# eHorglass.net
KiCad netlist of a schematic drawn in Altium Designer
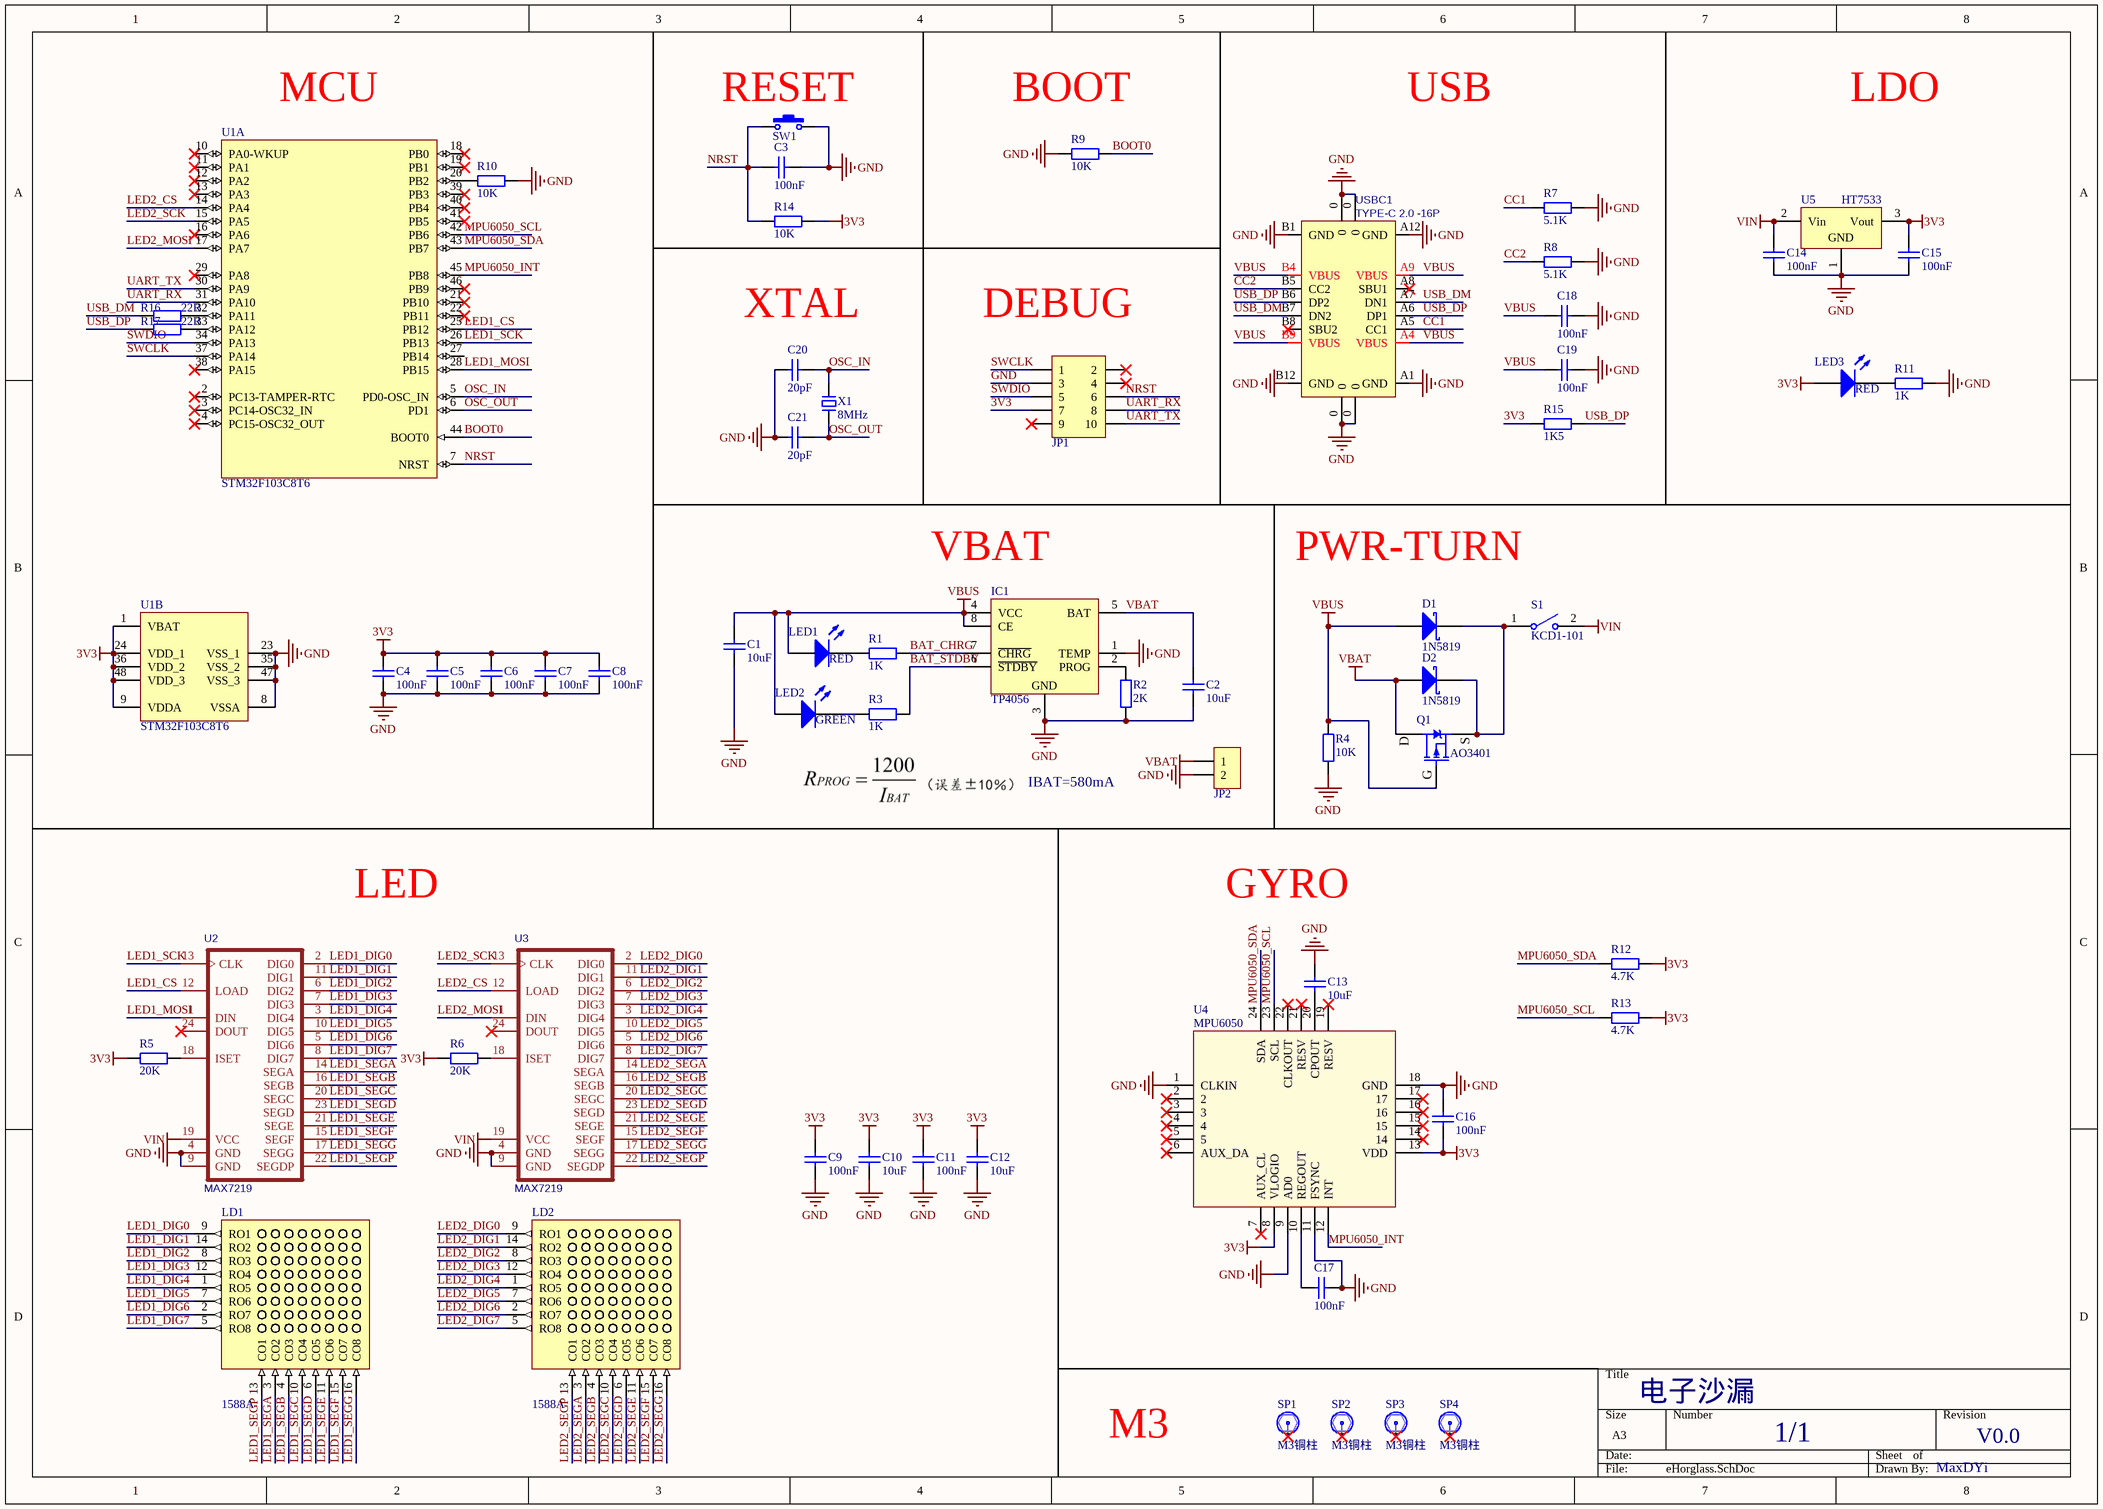
[diagram p0: eHorglass.SchDoc]

(export (version "E")
  (design (tool "Eeschema 10.0.6"))
  (components
    (comp (ref "C1")
      (value "10uF")
      (footprint "C0603_M")
      (description "贴片电容/MLCC电容")
      (libsource (lib "0.1 - 电阻-电容-电感-保险丝-晶振-晶体-磁珠-电位器-法拉电容-馈通电容") (part "C"))
    )
    (comp (ref "C2")
      (value "10uF")
      (footprint "C0603_M")
      (description "贴片电容/MLCC电容")
      (libsource (lib "0.1 - 电阻-电容-电感-保险丝-晶振-晶体-磁珠-电位器-法拉电容-馈通电容") (part "C"))
    )
    (comp (ref "C3")
      (value "100nF")
      (footprint "C0603_M")
      (description "贴片电容/MLCC电容")
      (libsource (lib "0.1 - 电阻-电容-电感-保险丝-晶振-晶体-磁珠-电位器-法拉电容-馈通电容") (part "C"))
    )
    (comp (ref "C4")
      (value "100nF")
      (footprint "C0603_M")
      (description "贴片电容/MLCC电容")
      (libsource (lib "0.1 - 电阻-电容-电感-保险丝-晶振-晶体-磁珠-电位器-法拉电容-馈通电容") (part "C"))
    )
    (comp (ref "C5")
      (value "100nF")
      (footprint "C0603_M")
      (description "贴片电容/MLCC电容")
      (libsource (lib "0.1 - 电阻-电容-电感-保险丝-晶振-晶体-磁珠-电位器-法拉电容-馈通电容") (part "C"))
    )
    (comp (ref "C6")
      (value "100nF")
      (footprint "C0603_M")
      (description "贴片电容/MLCC电容")
      (libsource (lib "0.1 - 电阻-电容-电感-保险丝-晶振-晶体-磁珠-电位器-法拉电容-馈通电容") (part "C"))
    )
    (comp (ref "C7")
      (value "100nF")
      (footprint "C0603_M")
      (description "贴片电容/MLCC电容")
      (libsource (lib "0.1 - 电阻-电容-电感-保险丝-晶振-晶体-磁珠-电位器-法拉电容-馈通电容") (part "C"))
    )
    (comp (ref "C8")
      (value "100nF")
      (footprint "C0603_M")
      (description "贴片电容/MLCC电容")
      (libsource (lib "0.1 - 电阻-电容-电感-保险丝-晶振-晶体-磁珠-电位器-法拉电容-馈通电容") (part "C"))
    )
    (comp (ref "C9")
      (value "100nF")
      (footprint "C0603_M")
      (description "贴片电容/MLCC电容")
      (libsource (lib "0.1 - 电阻-电容-电感-保险丝-晶振-晶体-磁珠-电位器-法拉电容-馈通电容") (part "C"))
    )
    (comp (ref "C10")
      (value "10uF")
      (footprint "C0603_M")
      (description "贴片电容/MLCC电容")
      (libsource (lib "0.1 - 电阻-电容-电感-保险丝-晶振-晶体-磁珠-电位器-法拉电容-馈通电容") (part "C"))
    )
    (comp (ref "C11")
      (value "100nF")
      (footprint "C0603_M")
      (description "贴片电容/MLCC电容")
      (libsource (lib "0.1 - 电阻-电容-电感-保险丝-晶振-晶体-磁珠-电位器-法拉电容-馈通电容") (part "C"))
    )
    (comp (ref "C12")
      (value "10uF")
      (footprint "C0603_M")
      (description "贴片电容/MLCC电容")
      (libsource (lib "0.1 - 电阻-电容-电感-保险丝-晶振-晶体-磁珠-电位器-法拉电容-馈通电容") (part "C"))
    )
    (comp (ref "C13")
      (value "10uF")
      (footprint "C0603_M")
      (description "贴片电容/MLCC电容")
      (libsource (lib "0.1 - 电阻-电容-电感-保险丝-晶振-晶体-磁珠-电位器-法拉电容-馈通电容") (part "C"))
    )
    (comp (ref "C14")
      (value "100nF")
      (footprint "C0603_M")
      (description "贴片电容/MLCC电容")
      (libsource (lib "0.1 - 电阻-电容-电感-保险丝-晶振-晶体-磁珠-电位器-法拉电容-馈通电容") (part "C"))
    )
    (comp (ref "C15")
      (value "100nF")
      (footprint "C0603_M")
      (description "贴片电容/MLCC电容")
      (libsource (lib "0.1 - 电阻-电容-电感-保险丝-晶振-晶体-磁珠-电位器-法拉电容-馈通电容") (part "C"))
    )
    (comp (ref "C16")
      (value "100nF")
      (footprint "C0603_M")
      (description "贴片电容/MLCC电容")
      (libsource (lib "0.1 - 电阻-电容-电感-保险丝-晶振-晶体-磁珠-电位器-法拉电容-馈通电容") (part "C"))
    )
    (comp (ref "C17")
      (value "100nF")
      (footprint "C0603_M")
      (description "贴片电容/MLCC电容")
      (libsource (lib "0.1 - 电阻-电容-电感-保险丝-晶振-晶体-磁珠-电位器-法拉电容-馈通电容") (part "C"))
    )
    (comp (ref "C18")
      (value "100nF")
      (footprint "C0603_M")
      (description "贴片电容/MLCC电容")
      (libsource (lib "0.1 - 电阻-电容-电感-保险丝-晶振-晶体-磁珠-电位器-法拉电容-馈通电容") (part "C"))
    )
    (comp (ref "C19")
      (value "100nF")
      (footprint "C0603_M")
      (description "贴片电容/MLCC电容")
      (libsource (lib "0.1 - 电阻-电容-电感-保险丝-晶振-晶体-磁珠-电位器-法拉电容-馈通电容") (part "C"))
    )
    (comp (ref "C20")
      (value "20pF")
      (footprint "C0603_M")
      (description "贴片电容/MLCC电容")
      (libsource (lib "0.1 - 电阻-电容-电感-保险丝-晶振-晶体-磁珠-电位器-法拉电容-馈通电容") (part "C"))
    )
    (comp (ref "C21")
      (value "20pF")
      (footprint "C0603_M")
      (description "贴片电容/MLCC电容")
      (libsource (lib "0.1 - 电阻-电容-电感-保险丝-晶振-晶体-磁珠-电位器-法拉电容-馈通电容") (part "C"))
    )
    (comp (ref "D1")
      (value "1N5819")
      (footprint "SOD-323")
      (description "肖特基二极管")
      (libsource (lib "0.2 - 二极管-TVS-ESD-整流桥-放电管") (part "1N5819"))
    )
    (comp (ref "D2")
      (value "1N5819")
      (footprint "SOD-323")
      (description "肖特基二极管")
      (libsource (lib "0.2 - 二极管-TVS-ESD-整流桥-放电管") (part "1N5819"))
    )
    (comp (ref "IC1")
      (value "TP4056")
      (footprint "SOIC-8_EP")
      (description "锂电池充电管理")
      (libsource (lib "0.7 - 电源类芯片") (part "TP4056"))
    )
    (comp (ref "JP1")
      (value "Header 5X2")
      (footprint "HDR2.54-LI-2x5P")
      (description "5*2P接插件")
      (libsource (lib "JD-Signal") (part "Header 5X2"))
    )
    (comp (ref "JP2")
      (value "HDR-1X2")
      (footprint "XH2.54-LI-2P")
      (description "2P接插件")
      (libsource (lib "5.5 - 2.54mm连接器(KF2EDGK_XH2.54_2.54排针排母)") (part "Header 2"))
    )
    (comp (ref "LD1")
      (value "1588A")
      (footprint "LED 8*8-32-FH")
      (description "共阴单色LED8*8点阵屏")
      (libsource (lib "1.3 - 数码管-TFT-OLED屏") (part "1588A"))
    )
    (comp (ref "LD2")
      (value "1588A")
      (footprint "LED 8*8-32-FH")
      (description "共阴单色LED8*8点阵屏")
      (libsource (lib "1.3 - 数码管-TFT-OLED屏") (part "1588A"))
    )
    (comp (ref "LED1")
      (value "RED")
      (footprint "LED0603_R")
      (description "贴片LED")
      (libsource (lib "0.3 - LED发光二极管-IR二极管_接收管-光耦") (part "LED"))
    )
    (comp (ref "LED2")
      (value "GREEN")
      (footprint "LED0603_G")
      (description "贴片LED")
      (libsource (lib "0.3 - LED发光二极管-IR二极管_接收管-光耦") (part "LED"))
    )
    (comp (ref "LED3")
      (value "RED")
      (footprint "LED0603_R")
      (description "贴片LED")
      (libsource (lib "0.3 - LED发光二极管-IR二极管_接收管-光耦") (part "LED"))
    )
    (comp (ref "Q1")
      (value "AO3401")
      (footprint "SOT23-3N")
      (description "P沟道 30V/4.2A")
      (libsource (lib "0.4 - 三极管-场效应管-可控硅") (part "AO3401"))
    )
    (comp (ref "R1")
      (value "1K")
      (footprint "R0603_M")
      (description "贴片电阻")
      (libsource (lib "0.1 - 电阻-电容-电感-保险丝-晶振-晶体-磁珠-电位器-法拉电容-馈通电容") (part "R"))
    )
    (comp (ref "R2")
      (value "2K")
      (footprint "R0603_M")
      (description "贴片电阻")
      (libsource (lib "0.1 - 电阻-电容-电感-保险丝-晶振-晶体-磁珠-电位器-法拉电容-馈通电容") (part "R"))
    )
    (comp (ref "R3")
      (value "1K")
      (footprint "R0603_M")
      (description "贴片电阻")
      (libsource (lib "0.1 - 电阻-电容-电感-保险丝-晶振-晶体-磁珠-电位器-法拉电容-馈通电容") (part "R"))
    )
    (comp (ref "R4")
      (value "10K")
      (footprint "R0603_M")
      (description "贴片电阻")
      (libsource (lib "0.1 - 电阻-电容-电感-保险丝-晶振-晶体-磁珠-电位器-法拉电容-馈通电容") (part "R"))
    )
    (comp (ref "R5")
      (value "20K")
      (footprint "R0603_M")
      (description "贴片电阻")
      (libsource (lib "0.1 - 电阻-电容-电感-保险丝-晶振-晶体-磁珠-电位器-法拉电容-馈通电容") (part "R"))
    )
    (comp (ref "R6")
      (value "20K")
      (footprint "R0603_M")
      (description "贴片电阻")
      (libsource (lib "0.1 - 电阻-电容-电感-保险丝-晶振-晶体-磁珠-电位器-法拉电容-馈通电容") (part "R"))
    )
    (comp (ref "R7")
      (value "5.1K")
      (footprint "R0603_M")
      (description "贴片电阻")
      (libsource (lib "0.1 - 电阻-电容-电感-保险丝-晶振-晶体-磁珠-电位器-法拉电容-馈通电容") (part "R"))
    )
    (comp (ref "R8")
      (value "5.1K")
      (footprint "R0603_M")
      (description "贴片电阻")
      (libsource (lib "0.1 - 电阻-电容-电感-保险丝-晶振-晶体-磁珠-电位器-法拉电容-馈通电容") (part "R"))
    )
    (comp (ref "R9")
      (value "10K")
      (footprint "R0603_M")
      (description "贴片电阻")
      (libsource (lib "0.1 - 电阻-电容-电感-保险丝-晶振-晶体-磁珠-电位器-法拉电容-馈通电容") (part "R"))
    )
    (comp (ref "R10")
      (value "10K")
      (footprint "R0603_M")
      (description "贴片电阻")
      (libsource (lib "0.1 - 电阻-电容-电感-保险丝-晶振-晶体-磁珠-电位器-法拉电容-馈通电容") (part "R"))
    )
    (comp (ref "R11")
      (value "1K")
      (footprint "R0603_M")
      (description "贴片电阻")
      (libsource (lib "0.1 - 电阻-电容-电感-保险丝-晶振-晶体-磁珠-电位器-法拉电容-馈通电容") (part "R"))
    )
    (comp (ref "R12")
      (value "4.7K")
      (footprint "R0603_M")
      (description "贴片电阻")
      (libsource (lib "0.1 - 电阻-电容-电感-保险丝-晶振-晶体-磁珠-电位器-法拉电容-馈通电容") (part "R"))
    )
    (comp (ref "R13")
      (value "4.7K")
      (footprint "R0603_M")
      (description "贴片电阻")
      (libsource (lib "0.1 - 电阻-电容-电感-保险丝-晶振-晶体-磁珠-电位器-法拉电容-馈通电容") (part "R"))
    )
    (comp (ref "R14")
      (value "10K")
      (footprint "R0603_M")
      (description "贴片电阻")
      (libsource (lib "0.1 - 电阻-电容-电感-保险丝-晶振-晶体-磁珠-电位器-法拉电容-馈通电容") (part "R"))
    )
    (comp (ref "R15")
      (value "1K5")
      (footprint "R0603_M")
      (description "贴片电阻")
      (libsource (lib "0.1 - 电阻-电容-电感-保险丝-晶振-晶体-磁珠-电位器-法拉电容-馈通电容") (part "R"))
    )
    (comp (ref "R16")
      (value "22R")
      (footprint "R0603_M")
      (description "贴片电阻")
      (libsource (lib "0.1 - 电阻-电容-电感-保险丝-晶振-晶体-磁珠-电位器-法拉电容-馈通电容") (part "R"))
    )
    (comp (ref "R17")
      (value "22R")
      (footprint "R0603_M")
      (description "贴片电阻")
      (libsource (lib "0.1 - 电阻-电容-电感-保险丝-晶振-晶体-磁珠-电位器-法拉电容-馈通电容") (part "R"))
    )
    (comp (ref "S1")
      (value "KCD1-101")
      (footprint "HDR2.54-LI-2P")
      (description "1路单刀船型开关")
      (libsource (lib "0.5 - 按键_开关_蜂鸣器_电池_测试点_Mark点_铜柱") (part "KCD1-101"))
    )
    (comp (ref "SP1")
      (value "M3铜柱")
      (footprint "M3x20+6_N")
      (description "铜柱")
      (libsource (lib "0.5 - 按键_开关_蜂鸣器_电池_测试点_Mark点_铜柱") (part "铜柱加头大焊盘"))
    )
    (comp (ref "SP2")
      (value "M3铜柱")
      (footprint "M3x20+6_N")
      (description "铜柱")
      (libsource (lib "0.5 - 按键_开关_蜂鸣器_电池_测试点_Mark点_铜柱") (part "铜柱加头大焊盘"))
    )
    (comp (ref "SP3")
      (value "M3铜柱")
      (footprint "M3x20+6_N")
      (description "铜柱")
      (libsource (lib "0.5 - 按键_开关_蜂鸣器_电池_测试点_Mark点_铜柱") (part "铜柱加头大焊盘"))
    )
    (comp (ref "SP4")
      (value "M3铜柱")
      (footprint "M3x20+6_N")
      (description "铜柱")
      (libsource (lib "0.5 - 按键_开关_蜂鸣器_电池_测试点_Mark点_铜柱") (part "铜柱加头大焊盘"))
    )
    (comp (ref "SW1")
      (value "3x6x5")
      (footprint "SW SMD-3*6*2.5")
      (description "3x6轻触开关")
      (libsource (lib "0.5 - 按键_开关_蜂鸣器_电池_测试点_Mark点_铜柱") (part "SW 3x6"))
    )
    (comp (ref "U1")
      (value "STM32F103C8T6")
      (footprint "LQFP48_N")
      (libsource (lib "2.4 - STM32 F1系列单片机") (part "STM32F103C8T6"))
    )
    (comp (ref "U2")
      (value "MAX7219")
      (footprint "SOIC-24W")
      (description "8位 LED驱动器")
      (libsource (lib "0.8 - 常见芯片") (part "MAX7219"))
    )
    (comp (ref "U3")
      (value "MAX7219")
      (footprint "SOIC-24W")
      (description "8位 LED驱动器")
      (libsource (lib "0.8 - 常见芯片") (part "MAX7219"))
    )
    (comp (ref "U4")
      (value "MPU6050")
      (footprint "QFN24-P50")
      (description "三轴加速度+三轴陀螺仪")
      (libsource (lib "0.9 - 传感器-存储器-模块") (part "MPU6050"))
    )
    (comp (ref "U5")
      (value "HT7533")
      (footprint "SOT89_N")
      (description "LDO线性稳压芯片")
      (libsource (lib "0.7 - 电源类芯片") (part "HT7533"))
    )
    (comp (ref "USBC1")
      (value "TYPE-C 2.0 -16P")
      (footprint "USB-C-SMD_16P")
      (description "USB2.0_Type-C_16Pin母座")
      (libsource (lib "0.6 - 电源_音频_USB Type-C_HDMI_XT60_5557_D-SUB_RJ45_SD-TF_SIM插座") (part "USB2.0_Type-C_16Pin"))
    )
    (comp (ref "X1")
      (value "8MHz")
      (footprint "OSC-5032-2P")
      (description "2脚无源晶振(谐振器）")
      (libsource (lib "0.1 - 电阻-电容-电感-保险丝-晶振-晶体-磁珠-电位器-法拉电容-馈通电容") (part "XTAL-2P"))
    )
  )
  (nets
    (net (code "1") (name "/BAT_CHRG") (class "Default")
      (node (ref "IC1") (pin "7") (pinfunction "~{CHRG}_7") (pintype "passive"))
      (node (ref "R1") (pin "1") (pinfunction "1_1") (pintype "passive"))
    )
    (net (code "2") (name "/BAT_STDBY") (class "Default")
      (node (ref "IC1") (pin "6") (pinfunction "~{STDBY}_6") (pintype "passive"))
      (node (ref "R3") (pin "1") (pinfunction "1_1") (pintype "passive"))
    )
    (net (code "3") (name "/BOOT0") (class "Default")
      (node (ref "R9") (pin "2") (pinfunction "2_2") (pintype "passive"))
      (node (ref "U1") (pin "44") (pinfunction "BOOT0_44") (pintype "input"))
    )
    (net (code "4") (name "/CC1") (class "Default")
      (node (ref "R7") (pin "2") (pinfunction "2_2") (pintype "passive"))
      (node (ref "USBC1") (pin "A5") (pinfunction "CC1_A5") (pintype "passive"))
    )
    (net (code "5") (name "/CC2") (class "Default")
      (node (ref "R8") (pin "2") (pinfunction "2_2") (pintype "passive"))
      (node (ref "USBC1") (pin "B5") (pinfunction "CC2_B5") (pintype "passive"))
    )
    (net (code "6") (name "/LED1_CS") (class "Default")
      (node (ref "U1") (pin "25") (pinfunction "PB12_25") (pintype "bidirectional"))
      (node (ref "U2") (pin "12") (pinfunction "LOAD_12") (pintype "passive"))
    )
    (net (code "7") (name "/LED1_DIG0") (class "Default")
      (node (ref "LD1") (pin "9") (pinfunction "RO1_9") (pintype "output"))
      (node (ref "U2") (pin "2") (pinfunction "DIG0_2") (pintype "passive"))
    )
    (net (code "8") (name "/LED1_DIG1") (class "Default")
      (node (ref "LD1") (pin "14") (pinfunction "RO2_14") (pintype "output"))
      (node (ref "U2") (pin "11") (pinfunction "DIG1_11") (pintype "passive"))
    )
    (net (code "9") (name "/LED1_DIG2") (class "Default")
      (node (ref "LD1") (pin "8") (pinfunction "RO3_8") (pintype "output"))
      (node (ref "U2") (pin "6") (pinfunction "DIG2_6") (pintype "passive"))
    )
    (net (code "10") (name "/LED1_DIG3") (class "Default")
      (node (ref "LD1") (pin "12") (pinfunction "RO4_12") (pintype "output"))
      (node (ref "U2") (pin "7") (pinfunction "DIG3_7") (pintype "passive"))
    )
    (net (code "11") (name "/LED1_DIG4") (class "Default")
      (node (ref "LD1") (pin "1") (pinfunction "RO5_1") (pintype "output"))
      (node (ref "U2") (pin "3") (pinfunction "DIG4_3") (pintype "passive"))
    )
    (net (code "12") (name "/LED1_DIG5") (class "Default")
      (node (ref "LD1") (pin "7") (pinfunction "RO6_7") (pintype "output"))
      (node (ref "U2") (pin "10") (pinfunction "DIG5_10") (pintype "passive"))
    )
    (net (code "13") (name "/LED1_DIG6") (class "Default")
      (node (ref "LD1") (pin "2") (pinfunction "RO7_2") (pintype "output"))
      (node (ref "U2") (pin "5") (pinfunction "DIG6_5") (pintype "passive"))
    )
    (net (code "14") (name "/LED1_DIG7") (class "Default")
      (node (ref "LD1") (pin "5") (pinfunction "RO8_5") (pintype "output"))
      (node (ref "U2") (pin "8") (pinfunction "DIG7_8") (pintype "passive"))
    )
    (net (code "15") (name "/LED1_MOSI") (class "Default")
      (node (ref "U1") (pin "28") (pinfunction "PB15_28") (pintype "bidirectional"))
      (node (ref "U2") (pin "1") (pinfunction "DIN_1") (pintype "passive"))
    )
    (net (code "16") (name "/LED1_SCK") (class "Default")
      (node (ref "U1") (pin "26") (pinfunction "PB13_26") (pintype "bidirectional"))
      (node (ref "U2") (pin "13") (pinfunction "CLK_13") (pintype "passive"))
    )
    (net (code "17") (name "/LED1_SEGA") (class "Default")
      (node (ref "LD1") (pin "3") (pinfunction "CO2_3") (pintype "input"))
      (node (ref "U2") (pin "14") (pinfunction "SEGA_14") (pintype "passive"))
    )
    (net (code "18") (name "/LED1_SEGB") (class "Default")
      (node (ref "LD1") (pin "4") (pinfunction "CO3_4") (pintype "input"))
      (node (ref "U2") (pin "16") (pinfunction "SEGB_16") (pintype "passive"))
    )
    (net (code "19") (name "/LED1_SEGC") (class "Default")
      (node (ref "LD1") (pin "10") (pinfunction "CO4_10") (pintype "input"))
      (node (ref "U2") (pin "20") (pinfunction "SEGC_20") (pintype "passive"))
    )
    (net (code "20") (name "/LED1_SEGD") (class "Default")
      (node (ref "LD1") (pin "6") (pinfunction "CO5_6") (pintype "input"))
      (node (ref "U2") (pin "23") (pinfunction "SEGD_23") (pintype "passive"))
    )
    (net (code "21") (name "/LED1_SEGE") (class "Default")
      (node (ref "LD1") (pin "11") (pinfunction "CO6_11") (pintype "input"))
      (node (ref "U2") (pin "21") (pinfunction "SEGE_21") (pintype "passive"))
    )
    (net (code "22") (name "/LED1_SEGF") (class "Default")
      (node (ref "LD1") (pin "15") (pinfunction "CO7_15") (pintype "input"))
      (node (ref "U2") (pin "15") (pinfunction "SEGF_15") (pintype "passive"))
    )
    (net (code "23") (name "/LED1_SEGG") (class "Default")
      (node (ref "LD1") (pin "16") (pinfunction "CO8_16") (pintype "input"))
      (node (ref "U2") (pin "17") (pinfunction "SEGG_17") (pintype "passive"))
    )
    (net (code "24") (name "/LED1_SEGP") (class "Default")
      (node (ref "LD1") (pin "13") (pinfunction "CO1_13") (pintype "input"))
      (node (ref "U2") (pin "22") (pinfunction "SEGDP_22") (pintype "passive"))
    )
    (net (code "25") (name "/LED2_CS") (class "Default")
      (node (ref "U1") (pin "14") (pinfunction "PA4_14") (pintype "bidirectional"))
      (node (ref "U3") (pin "12") (pinfunction "LOAD_12") (pintype "passive"))
    )
    (net (code "26") (name "/LED2_DIG0") (class "Default")
      (node (ref "LD2") (pin "9") (pinfunction "RO1_9") (pintype "output"))
      (node (ref "U3") (pin "2") (pinfunction "DIG0_2") (pintype "passive"))
    )
    (net (code "27") (name "/LED2_DIG1") (class "Default")
      (node (ref "LD2") (pin "14") (pinfunction "RO2_14") (pintype "output"))
      (node (ref "U3") (pin "11") (pinfunction "DIG1_11") (pintype "passive"))
    )
    (net (code "28") (name "/LED2_DIG2") (class "Default")
      (node (ref "LD2") (pin "8") (pinfunction "RO3_8") (pintype "output"))
      (node (ref "U3") (pin "6") (pinfunction "DIG2_6") (pintype "passive"))
    )
    (net (code "29") (name "/LED2_DIG3") (class "Default")
      (node (ref "LD2") (pin "12") (pinfunction "RO4_12") (pintype "output"))
      (node (ref "U3") (pin "7") (pinfunction "DIG3_7") (pintype "passive"))
    )
    (net (code "30") (name "/LED2_DIG4") (class "Default")
      (node (ref "LD2") (pin "1") (pinfunction "RO5_1") (pintype "output"))
      (node (ref "U3") (pin "3") (pinfunction "DIG4_3") (pintype "passive"))
    )
    (net (code "31") (name "/LED2_DIG5") (class "Default")
      (node (ref "LD2") (pin "7") (pinfunction "RO6_7") (pintype "output"))
      (node (ref "U3") (pin "10") (pinfunction "DIG5_10") (pintype "passive"))
    )
    (net (code "32") (name "/LED2_DIG6") (class "Default")
      (node (ref "LD2") (pin "2") (pinfunction "RO7_2") (pintype "output"))
      (node (ref "U3") (pin "5") (pinfunction "DIG6_5") (pintype "passive"))
    )
    (net (code "33") (name "/LED2_DIG7") (class "Default")
      (node (ref "LD2") (pin "5") (pinfunction "RO8_5") (pintype "output"))
      (node (ref "U3") (pin "8") (pinfunction "DIG7_8") (pintype "passive"))
    )
    (net (code "34") (name "/LED2_MOSI") (class "Default")
      (node (ref "U1") (pin "17") (pinfunction "PA7_17") (pintype "bidirectional"))
      (node (ref "U3") (pin "1") (pinfunction "DIN_1") (pintype "passive"))
    )
    (net (code "35") (name "/LED2_SCK") (class "Default")
      (node (ref "U1") (pin "15") (pinfunction "PA5_15") (pintype "bidirectional"))
      (node (ref "U3") (pin "13") (pinfunction "CLK_13") (pintype "passive"))
    )
    (net (code "36") (name "/LED2_SEGA") (class "Default")
      (node (ref "LD2") (pin "3") (pinfunction "CO2_3") (pintype "input"))
      (node (ref "U3") (pin "14") (pinfunction "SEGA_14") (pintype "passive"))
    )
    (net (code "37") (name "/LED2_SEGB") (class "Default")
      (node (ref "LD2") (pin "4") (pinfunction "CO3_4") (pintype "input"))
      (node (ref "U3") (pin "16") (pinfunction "SEGB_16") (pintype "passive"))
    )
    (net (code "38") (name "/LED2_SEGC") (class "Default")
      (node (ref "LD2") (pin "10") (pinfunction "CO4_10") (pintype "input"))
      (node (ref "U3") (pin "20") (pinfunction "SEGC_20") (pintype "passive"))
    )
    (net (code "39") (name "/LED2_SEGD") (class "Default")
      (node (ref "LD2") (pin "6") (pinfunction "CO5_6") (pintype "input"))
      (node (ref "U3") (pin "23") (pinfunction "SEGD_23") (pintype "passive"))
    )
    (net (code "40") (name "/LED2_SEGE") (class "Default")
      (node (ref "LD2") (pin "11") (pinfunction "CO6_11") (pintype "input"))
      (node (ref "U3") (pin "21") (pinfunction "SEGE_21") (pintype "passive"))
    )
    (net (code "41") (name "/LED2_SEGF") (class "Default")
      (node (ref "LD2") (pin "15") (pinfunction "CO7_15") (pintype "input"))
      (node (ref "U3") (pin "15") (pinfunction "SEGF_15") (pintype "passive"))
    )
    (net (code "42") (name "/LED2_SEGG") (class "Default")
      (node (ref "LD2") (pin "16") (pinfunction "CO8_16") (pintype "input"))
      (node (ref "U3") (pin "17") (pinfunction "SEGG_17") (pintype "passive"))
    )
    (net (code "43") (name "/LED2_SEGP") (class "Default")
      (node (ref "LD2") (pin "13") (pinfunction "CO1_13") (pintype "input"))
      (node (ref "U3") (pin "22") (pinfunction "SEGDP_22") (pintype "passive"))
    )
    (net (code "44") (name "/MPU6050_INT") (class "Default")
      (node (ref "U1") (pin "45") (pinfunction "PB8_45") (pintype "bidirectional"))
      (node (ref "U4") (pin "12") (pinfunction "INT_12") (pintype "passive"))
    )
    (net (code "45") (name "/MPU6050_SCL") (class "Default")
      (node (ref "R13") (pin "2") (pinfunction "2_2") (pintype "passive"))
      (node (ref "U1") (pin "42") (pinfunction "PB6_42") (pintype "bidirectional"))
      (node (ref "U4") (pin "23") (pinfunction "SCL_23") (pintype "passive"))
    )
    (net (code "46") (name "/MPU6050_SDA") (class "Default")
      (node (ref "R12") (pin "2") (pinfunction "2_2") (pintype "passive"))
      (node (ref "U1") (pin "43") (pinfunction "PB7_43") (pintype "bidirectional"))
      (node (ref "U4") (pin "24") (pinfunction "SDA_24") (pintype "passive"))
    )
    (net (code "47") (name "/NRST") (class "Default")
      (node (ref "C3") (pin "2") (pinfunction "2_2") (pintype "passive"))
      (node (ref "JP1") (pin "6") (pinfunction "6_6") (pintype "passive"))
      (node (ref "R14") (pin "1") (pinfunction "1_1") (pintype "passive"))
      (node (ref "SW1") (pin "1") (pinfunction "1_1") (pintype "passive"))
      (node (ref "U1") (pin "7") (pinfunction "NRST_7") (pintype "bidirectional"))
    )
    (net (code "48") (name "/OSC_IN") (class "Default")
      (node (ref "C20") (pin "2") (pinfunction "2_2") (pintype "passive"))
      (node (ref "U1") (pin "5") (pinfunction "PD0-OSC_IN_5") (pintype "bidirectional"))
      (node (ref "X1") (pin "2") (pinfunction "2_2") (pintype "passive"))
    )
    (net (code "49") (name "/OSC_OUT") (class "Default")
      (node (ref "C21") (pin "1") (pinfunction "1_1") (pintype "passive"))
      (node (ref "U1") (pin "6") (pinfunction "PD1_6") (pintype "bidirectional"))
      (node (ref "X1") (pin "1") (pinfunction "1_1") (pintype "passive"))
    )
    (net (code "50") (name "/SWCLK") (class "Default")
      (node (ref "JP1") (pin "1") (pinfunction "1_1") (pintype "passive"))
      (node (ref "U1") (pin "37") (pinfunction "PA14_37") (pintype "bidirectional"))
    )
    (net (code "51") (name "/SWDIO") (class "Default")
      (node (ref "JP1") (pin "5") (pinfunction "5_5") (pintype "passive"))
      (node (ref "U1") (pin "34") (pinfunction "PA13_34") (pintype "bidirectional"))
    )
    (net (code "52") (name "/UART_RX") (class "Default")
      (node (ref "JP1") (pin "8") (pinfunction "8_8") (pintype "passive"))
      (node (ref "U1") (pin "31") (pinfunction "PA10_31") (pintype "bidirectional"))
    )
    (net (code "53") (name "/UART_TX") (class "Default")
      (node (ref "JP1") (pin "10") (pinfunction "10_10") (pintype "passive"))
      (node (ref "U1") (pin "30") (pinfunction "PA9_30") (pintype "bidirectional"))
    )
    (net (code "54") (name "/USB_DM") (class "Default")
      (node (ref "R16") (pin "1") (pinfunction "1_1") (pintype "passive"))
      (node (ref "USBC1") (pin "A7") (pinfunction "DN1_A7") (pintype "passive"))
      (node (ref "USBC1") (pin "B7") (pinfunction "DN2_B7") (pintype "passive"))
    )
    (net (code "55") (name "/USB_DP") (class "Default")
      (node (ref "R15") (pin "2") (pinfunction "2_2") (pintype "passive"))
      (node (ref "R17") (pin "1") (pinfunction "1_1") (pintype "passive"))
      (node (ref "USBC1") (pin "A6") (pinfunction "DP1_A6") (pintype "passive"))
      (node (ref "USBC1") (pin "B6") (pinfunction "DP2_B6") (pintype "passive"))
    )
    (net (code "56") (name "3V3") (class "Default")
      (node (ref "C10") (pin "2") (pinfunction "2_2") (pintype "passive"))
      (node (ref "C11") (pin "2") (pinfunction "2_2") (pintype "passive"))
      (node (ref "C12") (pin "2") (pinfunction "2_2") (pintype "passive"))
      (node (ref "C15") (pin "2") (pinfunction "2_2") (pintype "passive"))
      (node (ref "C16") (pin "2") (pinfunction "2_2") (pintype "passive"))
      (node (ref "C4") (pin "2") (pinfunction "2_2") (pintype "passive"))
      (node (ref "C5") (pin "2") (pinfunction "2_2") (pintype "passive"))
      (node (ref "C6") (pin "2") (pinfunction "2_2") (pintype "passive"))
      (node (ref "C7") (pin "2") (pinfunction "2_2") (pintype "passive"))
      (node (ref "C8") (pin "2") (pinfunction "2_2") (pintype "passive"))
      (node (ref "C9") (pin "2") (pinfunction "2_2") (pintype "passive"))
      (node (ref "JP1") (pin "7") (pinfunction "7_7") (pintype "passive"))
      (node (ref "LED3") (pin "1") (pinfunction "A_1") (pintype "passive"))
      (node (ref "R12") (pin "1") (pinfunction "1_1") (pintype "passive"))
      (node (ref "R13") (pin "1") (pinfunction "1_1") (pintype "passive"))
      (node (ref "R14") (pin "2") (pinfunction "2_2") (pintype "passive"))
      (node (ref "R15") (pin "1") (pinfunction "1_1") (pintype "passive"))
      (node (ref "R5") (pin "2") (pinfunction "2_2") (pintype "passive"))
      (node (ref "R6") (pin "2") (pinfunction "2_2") (pintype "passive"))
      (node (ref "U1") (pin "1") (pinfunction "VBAT_1") (pintype "power_in"))
      (node (ref "U1") (pin "24") (pinfunction "VDD_1_24") (pintype "power_in"))
      (node (ref "U1") (pin "36") (pinfunction "VDD_2_36") (pintype "power_in"))
      (node (ref "U1") (pin "48") (pinfunction "VDD_3_48") (pintype "power_in"))
      (node (ref "U1") (pin "9") (pinfunction "VDDA_9") (pintype "power_in"))
      (node (ref "U4") (pin "13") (pinfunction "VDD_13") (pintype "passive"))
      (node (ref "U4") (pin "8") (pinfunction "VLOGIO_8") (pintype "passive"))
      (node (ref "U5") (pin "3") (pinfunction "Vout_3") (pintype "passive"))
    )
    (net (code "57") (name "GND") (class "Default")
      (node (ref "C1") (pin "1") (pinfunction "1_1") (pintype "passive"))
      (node (ref "C10") (pin "1") (pinfunction "1_1") (pintype "passive"))
      (node (ref "C11") (pin "1") (pinfunction "1_1") (pintype "passive"))
      (node (ref "C12") (pin "1") (pinfunction "1_1") (pintype "passive"))
      (node (ref "C13") (pin "1") (pinfunction "1_1") (pintype "passive"))
      (node (ref "C14") (pin "1") (pinfunction "1_1") (pintype "passive"))
      (node (ref "C15") (pin "1") (pinfunction "1_1") (pintype "passive"))
      (node (ref "C16") (pin "1") (pinfunction "1_1") (pintype "passive"))
      (node (ref "C17") (pin "1") (pinfunction "1_1") (pintype "passive"))
      (node (ref "C18") (pin "2") (pinfunction "2_2") (pintype "passive"))
      (node (ref "C19") (pin "2") (pinfunction "2_2") (pintype "passive"))
      (node (ref "C2") (pin "1") (pinfunction "1_1") (pintype "passive"))
      (node (ref "C20") (pin "1") (pinfunction "1_1") (pintype "passive"))
      (node (ref "C21") (pin "2") (pinfunction "2_2") (pintype "passive"))
      (node (ref "C3") (pin "1") (pinfunction "1_1") (pintype "passive"))
      (node (ref "C4") (pin "1") (pinfunction "1_1") (pintype "passive"))
      (node (ref "C5") (pin "1") (pinfunction "1_1") (pintype "passive"))
      (node (ref "C6") (pin "1") (pinfunction "1_1") (pintype "passive"))
      (node (ref "C7") (pin "1") (pinfunction "1_1") (pintype "passive"))
      (node (ref "C8") (pin "1") (pinfunction "1_1") (pintype "passive"))
      (node (ref "C9") (pin "1") (pinfunction "1_1") (pintype "passive"))
      (node (ref "IC1") (pin "1") (pinfunction "TEMP_1") (pintype "passive"))
      (node (ref "IC1") (pin "3") (pinfunction "GND_3") (pintype "passive"))
      (node (ref "JP1") (pin "3") (pinfunction "3_3") (pintype "passive"))
      (node (ref "JP2") (pin "2") (pinfunction "2_2") (pintype "passive"))
      (node (ref "R10") (pin "1") (pinfunction "1_1") (pintype "passive"))
      (node (ref "R11") (pin "1") (pinfunction "1_1") (pintype "passive"))
      (node (ref "R2") (pin "1") (pinfunction "1_1") (pintype "passive"))
      (node (ref "R4") (pin "1") (pinfunction "1_1") (pintype "passive"))
      (node (ref "R7") (pin "1") (pinfunction "1_1") (pintype "passive"))
      (node (ref "R8") (pin "1") (pinfunction "1_1") (pintype "passive"))
      (node (ref "R9") (pin "1") (pinfunction "1_1") (pintype "passive"))
      (node (ref "SW1") (pin "2") (pinfunction "2_2") (pintype "passive"))
      (node (ref "U1") (pin "23") (pinfunction "VSS_1_23") (pintype "power_in"))
      (node (ref "U1") (pin "35") (pinfunction "VSS_2_35") (pintype "power_in"))
      (node (ref "U1") (pin "47") (pinfunction "VSS_3_47") (pintype "power_in"))
      (node (ref "U1") (pin "8") (pinfunction "VSSA_8") (pintype "power_in"))
      (node (ref "U2") (pin "4") (pinfunction "GND_4") (pintype "passive"))
      (node (ref "U2") (pin "9") (pinfunction "GND_9") (pintype "passive"))
      (node (ref "U3") (pin "4") (pinfunction "GND_4") (pintype "passive"))
      (node (ref "U3") (pin "9") (pinfunction "GND_9") (pintype "passive"))
      (node (ref "U4") (pin "1") (pinfunction "CLKIN_1") (pintype "passive"))
      (node (ref "U4") (pin "11") (pinfunction "FSYNC_11") (pintype "passive"))
      (node (ref "U4") (pin "18") (pinfunction "GND_18") (pintype "passive"))
      (node (ref "U4") (pin "9") (pinfunction "AD0_9") (pintype "passive"))
      (node (ref "U5") (pin "1") (pinfunction "GND_1") (pintype "passive"))
      (node (ref "USBC1") (pin "0") (pinfunction "0_0") (pintype "passive"))
      (node (ref "USBC1") (pin "A1") (pinfunction "GND_A1") (pintype "passive"))
      (node (ref "USBC1") (pin "A12") (pinfunction "GND_A12") (pintype "passive"))
      (node (ref "USBC1") (pin "B1") (pinfunction "GND_B1") (pintype "passive"))
      (node (ref "USBC1") (pin "B12") (pinfunction "GND_B12") (pintype "passive"))
    )
    (net (code "58") (name "Net-(D1-K)") (class "Default")
      (node (ref "D1") (pin "2") (pinfunction "K_2") (pintype "passive"))
      (node (ref "D2") (pin "2") (pinfunction "K_2") (pintype "passive"))
      (node (ref "Q1") (pin "2") (pinfunction "S_2") (pintype "passive"))
      (node (ref "S1") (pin "1") (pinfunction "1_1") (pintype "passive"))
    )
    (net (code "59") (name "Net-(IC1-PROG)") (class "Default")
      (node (ref "IC1") (pin "2") (pinfunction "PROG_2") (pintype "passive"))
      (node (ref "R2") (pin "2") (pinfunction "2_2") (pintype "passive"))
    )
    (net (code "60") (name "Net-(LED1-K)") (class "Default")
      (node (ref "LED1") (pin "2") (pinfunction "K_2") (pintype "passive"))
      (node (ref "R1") (pin "2") (pinfunction "2_2") (pintype "passive"))
    )
    (net (code "61") (name "Net-(LED2-K)") (class "Default")
      (node (ref "LED2") (pin "2") (pinfunction "K_2") (pintype "passive"))
      (node (ref "R3") (pin "2") (pinfunction "2_2") (pintype "passive"))
    )
    (net (code "62") (name "Net-(LED3-K)") (class "Default")
      (node (ref "LED3") (pin "2") (pinfunction "K_2") (pintype "passive"))
      (node (ref "R11") (pin "2") (pinfunction "2_2") (pintype "passive"))
    )
    (net (code "63") (name "Net-(U1A-PA11)") (class "Default")
      (node (ref "R16") (pin "2") (pinfunction "2_2") (pintype "passive"))
      (node (ref "U1") (pin "32") (pinfunction "PA11_32") (pintype "bidirectional"))
    )
    (net (code "64") (name "Net-(U1A-PA12)") (class "Default")
      (node (ref "R17") (pin "2") (pinfunction "2_2") (pintype "passive"))
      (node (ref "U1") (pin "33") (pinfunction "PA12_33") (pintype "bidirectional"))
    )
    (net (code "65") (name "Net-(U1A-PB2)") (class "Default")
      (node (ref "R10") (pin "2") (pinfunction "2_2") (pintype "passive"))
      (node (ref "U1") (pin "20") (pinfunction "PB2_20") (pintype "bidirectional"))
    )
    (net (code "66") (name "Net-(U2-ISET)") (class "Default")
      (node (ref "R5") (pin "1") (pinfunction "1_1") (pintype "passive"))
      (node (ref "U2") (pin "18") (pinfunction "ISET_18") (pintype "passive"))
    )
    (net (code "67") (name "Net-(U3-ISET)") (class "Default")
      (node (ref "R6") (pin "1") (pinfunction "1_1") (pintype "passive"))
      (node (ref "U3") (pin "18") (pinfunction "ISET_18") (pintype "passive"))
    )
    (net (code "68") (name "Net-(U4-CPOUT)") (class "Default")
      (node (ref "C13") (pin "2") (pinfunction "2_2") (pintype "passive"))
      (node (ref "U4") (pin "20") (pinfunction "CPOUT_20") (pintype "passive"))
    )
    (net (code "69") (name "Net-(U4-REGOUT)") (class "Default")
      (node (ref "C17") (pin "2") (pinfunction "2_2") (pintype "passive"))
      (node (ref "U4") (pin "10") (pinfunction "REGOUT_10") (pintype "passive"))
    )
    (net (code "70") (name "VBAT") (class "Default")
      (node (ref "C2") (pin "2") (pinfunction "2_2") (pintype "passive"))
      (node (ref "D2") (pin "1") (pinfunction "A_1") (pintype "passive"))
      (node (ref "IC1") (pin "5") (pinfunction "BAT_5") (pintype "passive"))
      (node (ref "JP2") (pin "1") (pinfunction "1_1") (pintype "passive"))
      (node (ref "Q1") (pin "3") (pinfunction "D_3") (pintype "passive"))
    )
    (net (code "71") (name "VBUS") (class "Default")
      (node (ref "C1") (pin "2") (pinfunction "2_2") (pintype "passive"))
      (node (ref "C18") (pin "1") (pinfunction "1_1") (pintype "passive"))
      (node (ref "C19") (pin "1") (pinfunction "1_1") (pintype "passive"))
      (node (ref "D1") (pin "1") (pinfunction "A_1") (pintype "passive"))
      (node (ref "IC1") (pin "4") (pinfunction "VCC_4") (pintype "passive"))
      (node (ref "IC1") (pin "8") (pinfunction "CE_8") (pintype "passive"))
      (node (ref "LED1") (pin "1") (pinfunction "A_1") (pintype "passive"))
      (node (ref "LED2") (pin "1") (pinfunction "A_1") (pintype "passive"))
      (node (ref "Q1") (pin "1") (pinfunction "G_1") (pintype "passive"))
      (node (ref "R4") (pin "2") (pinfunction "2_2") (pintype "passive"))
      (node (ref "USBC1") (pin "A4") (pinfunction "VBUS_A4") (pintype "passive"))
      (node (ref "USBC1") (pin "A9") (pinfunction "VBUS_A9") (pintype "passive"))
      (node (ref "USBC1") (pin "B4") (pinfunction "VBUS_B4") (pintype "passive"))
      (node (ref "USBC1") (pin "B9") (pinfunction "VBUS_B9") (pintype "passive"))
    )
    (net (code "72") (name "VIN") (class "Default")
      (node (ref "C14") (pin "2") (pinfunction "2_2") (pintype "passive"))
      (node (ref "S1") (pin "2") (pinfunction "2_2") (pintype "passive"))
      (node (ref "U2") (pin "19") (pinfunction "VCC_19") (pintype "passive"))
      (node (ref "U3") (pin "19") (pinfunction "VCC_19") (pintype "passive"))
      (node (ref "U5") (pin "2") (pinfunction "Vin_2") (pintype "passive"))
    )
    (net (code "73") (name "unconnected-(JP1-Pad2)") (class "Default")
      (node (ref "JP1") (pin "2") (pinfunction "2_2") (pintype "passive+no_connect"))
    )
    (net (code "74") (name "unconnected-(JP1-Pad4)") (class "Default")
      (node (ref "JP1") (pin "4") (pinfunction "4_4") (pintype "passive+no_connect"))
    )
    (net (code "75") (name "unconnected-(JP1-Pad9)") (class "Default")
      (node (ref "JP1") (pin "9") (pinfunction "9_9") (pintype "passive+no_connect"))
    )
    (net (code "76") (name "unconnected-(SP1-Pad1)") (class "Default")
      (node (ref "SP1") (pin "1") (pinfunction "1_1") (pintype "passive+no_connect"))
    )
    (net (code "77") (name "unconnected-(SP2-Pad1)") (class "Default")
      (node (ref "SP2") (pin "1") (pinfunction "1_1") (pintype "passive+no_connect"))
    )
    (net (code "78") (name "unconnected-(SP3-Pad1)") (class "Default")
      (node (ref "SP3") (pin "1") (pinfunction "1_1") (pintype "passive+no_connect"))
    )
    (net (code "79") (name "unconnected-(SP4-Pad1)") (class "Default")
      (node (ref "SP4") (pin "1") (pinfunction "1_1") (pintype "passive+no_connect"))
    )
    (net (code "80") (name "unconnected-(U1A-PA0-WKUP-Pad10)") (class "Default")
      (node (ref "U1") (pin "10") (pinfunction "PA0-WKUP_10") (pintype "bidirectional+no_connect"))
    )
    (net (code "81") (name "unconnected-(U1A-PA1-Pad11)") (class "Default")
      (node (ref "U1") (pin "11") (pinfunction "PA1_11") (pintype "bidirectional+no_connect"))
    )
    (net (code "82") (name "unconnected-(U1A-PA2-Pad12)") (class "Default")
      (node (ref "U1") (pin "12") (pinfunction "PA2_12") (pintype "bidirectional+no_connect"))
    )
    (net (code "83") (name "unconnected-(U1A-PA3-Pad13)") (class "Default")
      (node (ref "U1") (pin "13") (pinfunction "PA3_13") (pintype "bidirectional+no_connect"))
    )
    (net (code "84") (name "unconnected-(U1A-PA6-Pad16)") (class "Default")
      (node (ref "U1") (pin "16") (pinfunction "PA6_16") (pintype "bidirectional+no_connect"))
    )
    (net (code "85") (name "unconnected-(U1A-PA8-Pad29)") (class "Default")
      (node (ref "U1") (pin "29") (pinfunction "PA8_29") (pintype "bidirectional+no_connect"))
    )
    (net (code "86") (name "unconnected-(U1A-PA15-Pad38)") (class "Default")
      (node (ref "U1") (pin "38") (pinfunction "PA15_38") (pintype "bidirectional+no_connect"))
    )
    (net (code "87") (name "unconnected-(U1A-PB0-Pad18)") (class "Default")
      (node (ref "U1") (pin "18") (pinfunction "PB0_18") (pintype "bidirectional+no_connect"))
    )
    (net (code "88") (name "unconnected-(U1A-PB1-Pad19)") (class "Default")
      (node (ref "U1") (pin "19") (pinfunction "PB1_19") (pintype "bidirectional+no_connect"))
    )
    (net (code "89") (name "unconnected-(U1A-PB3-Pad39)") (class "Default")
      (node (ref "U1") (pin "39") (pinfunction "PB3_39") (pintype "bidirectional+no_connect"))
    )
    (net (code "90") (name "unconnected-(U1A-PB4-Pad40)") (class "Default")
      (node (ref "U1") (pin "40") (pinfunction "PB4_40") (pintype "bidirectional+no_connect"))
    )
    (net (code "91") (name "unconnected-(U1A-PB5-Pad41)") (class "Default")
      (node (ref "U1") (pin "41") (pinfunction "PB5_41") (pintype "bidirectional+no_connect"))
    )
    (net (code "92") (name "unconnected-(U1A-PB9-Pad46)") (class "Default")
      (node (ref "U1") (pin "46") (pinfunction "PB9_46") (pintype "bidirectional+no_connect"))
    )
    (net (code "93") (name "unconnected-(U1A-PB10-Pad21)") (class "Default")
      (node (ref "U1") (pin "21") (pinfunction "PB10_21") (pintype "bidirectional+no_connect"))
    )
    (net (code "94") (name "unconnected-(U1A-PB11-Pad22)") (class "Default")
      (node (ref "U1") (pin "22") (pinfunction "PB11_22") (pintype "bidirectional+no_connect"))
    )
    (net (code "95") (name "unconnected-(U1A-PB14-Pad27)") (class "Default")
      (node (ref "U1") (pin "27") (pinfunction "PB14_27") (pintype "bidirectional"))
    )
    (net (code "96") (name "unconnected-(U1A-PC13-TAMPER-RTC-Pad2)") (class "Default")
      (node (ref "U1") (pin "2") (pinfunction "PC13-TAMPER-RTC_2") (pintype "bidirectional+no_connect"))
    )
    (net (code "97") (name "unconnected-(U1A-PC14-OSC32_IN-Pad3)") (class "Default")
      (node (ref "U1") (pin "3") (pinfunction "PC14-OSC32_IN_3") (pintype "bidirectional+no_connect"))
    )
    (net (code "98") (name "unconnected-(U1A-PC15-OSC32_OUT-Pad4)") (class "Default")
      (node (ref "U1") (pin "4") (pinfunction "PC15-OSC32_OUT_4") (pintype "bidirectional+no_connect"))
    )
    (net (code "99") (name "unconnected-(U2-DOUT-Pad24)") (class "Default")
      (node (ref "U2") (pin "24") (pinfunction "DOUT_24") (pintype "passive+no_connect"))
    )
    (net (code "100") (name "unconnected-(U3-DOUT-Pad24)") (class "Default")
      (node (ref "U3") (pin "24") (pinfunction "DOUT_24") (pintype "passive+no_connect"))
    )
    (net (code "101") (name "unconnected-(U4-AUX_CL-Pad7)") (class "Default")
      (node (ref "U4") (pin "7") (pinfunction "AUX_CL_7") (pintype "passive+no_connect"))
    )
    (net (code "102") (name "unconnected-(U4-AUX_DA-Pad6)") (class "Default")
      (node (ref "U4") (pin "6") (pinfunction "AUX_DA_6") (pintype "passive+no_connect"))
    )
    (net (code "103") (name "unconnected-(U4-CLKOUT-Pad22)") (class "Default")
      (node (ref "U4") (pin "22") (pinfunction "CLKOUT_22") (pintype "passive+no_connect"))
    )
    (net (code "104") (name "unconnected-(U4-Pad2)") (class "Default")
      (node (ref "U4") (pin "2") (pinfunction "2_2") (pintype "passive+no_connect"))
    )
    (net (code "105") (name "unconnected-(U4-Pad3)") (class "Default")
      (node (ref "U4") (pin "3") (pinfunction "3_3") (pintype "passive+no_connect"))
    )
    (net (code "106") (name "unconnected-(U4-Pad4)") (class "Default")
      (node (ref "U4") (pin "4") (pinfunction "4_4") (pintype "passive+no_connect"))
    )
    (net (code "107") (name "unconnected-(U4-Pad5)") (class "Default")
      (node (ref "U4") (pin "5") (pinfunction "5_5") (pintype "passive+no_connect"))
    )
    (net (code "108") (name "unconnected-(U4-Pad14)") (class "Default")
      (node (ref "U4") (pin "14") (pinfunction "14_14") (pintype "passive+no_connect"))
    )
    (net (code "109") (name "unconnected-(U4-Pad15)") (class "Default")
      (node (ref "U4") (pin "15") (pinfunction "15_15") (pintype "passive+no_connect"))
    )
    (net (code "110") (name "unconnected-(U4-Pad16)") (class "Default")
      (node (ref "U4") (pin "16") (pinfunction "16_16") (pintype "passive+no_connect"))
    )
    (net (code "111") (name "unconnected-(U4-Pad17)") (class "Default")
      (node (ref "U4") (pin "17") (pinfunction "17_17") (pintype "passive+no_connect"))
    )
    (net (code "112") (name "unconnected-(U4-RESV-Pad19)") (class "Default")
      (node (ref "U4") (pin "19") (pinfunction "RESV_19") (pintype "passive+no_connect"))
    )
    (net (code "113") (name "unconnected-(U4-RESV-Pad21)") (class "Default")
      (node (ref "U4") (pin "21") (pinfunction "RESV_21") (pintype "passive+no_connect"))
    )
    (net (code "114") (name "unconnected-(USBC1-SBU1-PadA8)") (class "Default")
      (node (ref "USBC1") (pin "A8") (pinfunction "SBU1_A8") (pintype "passive+no_connect"))
    )
    (net (code "115") (name "unconnected-(USBC1-SBU2-PadB8)") (class "Default")
      (node (ref "USBC1") (pin "B8") (pinfunction "SBU2_B8") (pintype "passive+no_connect"))
    )
  )
)
